# hd-gs.net
KiCad netlist of a schematic drawn in Altium Designer
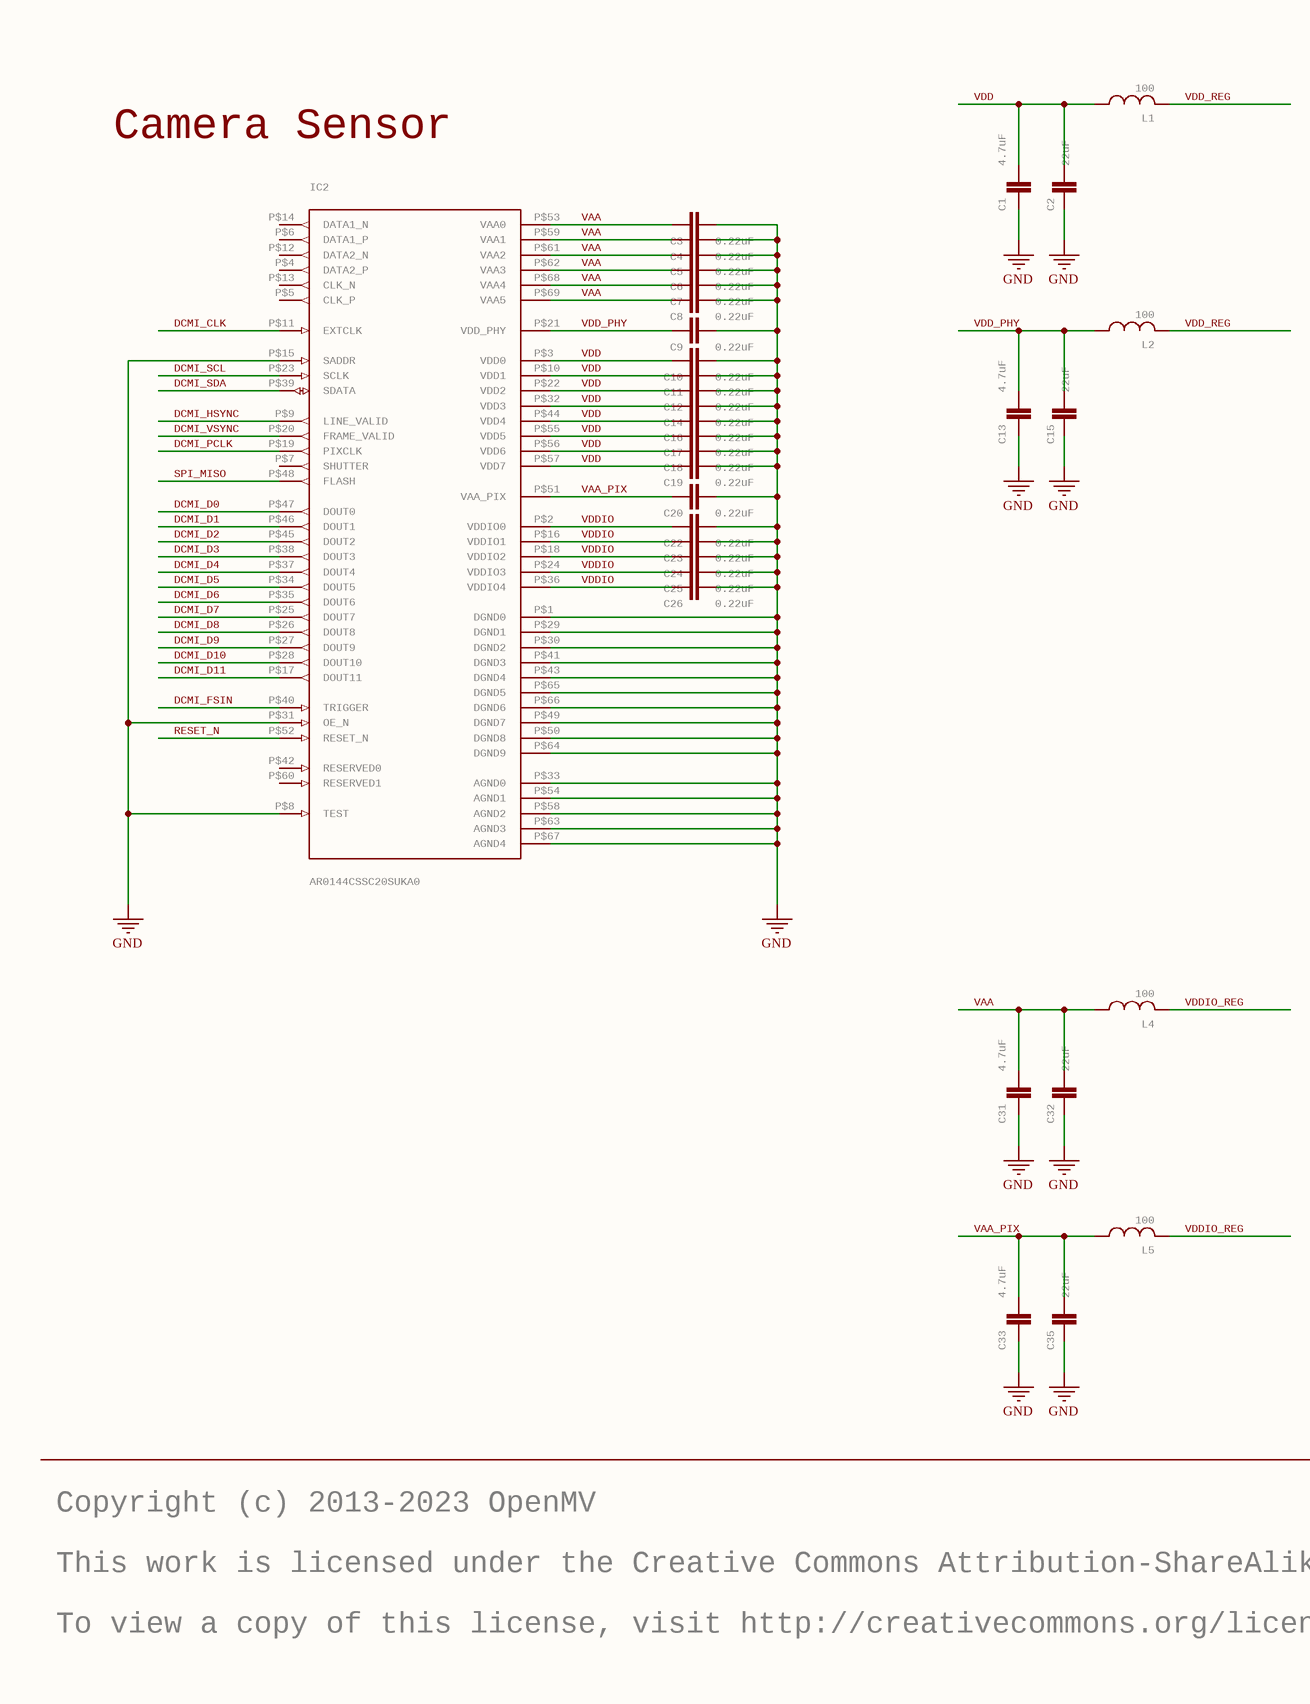
[diagram p0: hd-gs.SchDoc, left]
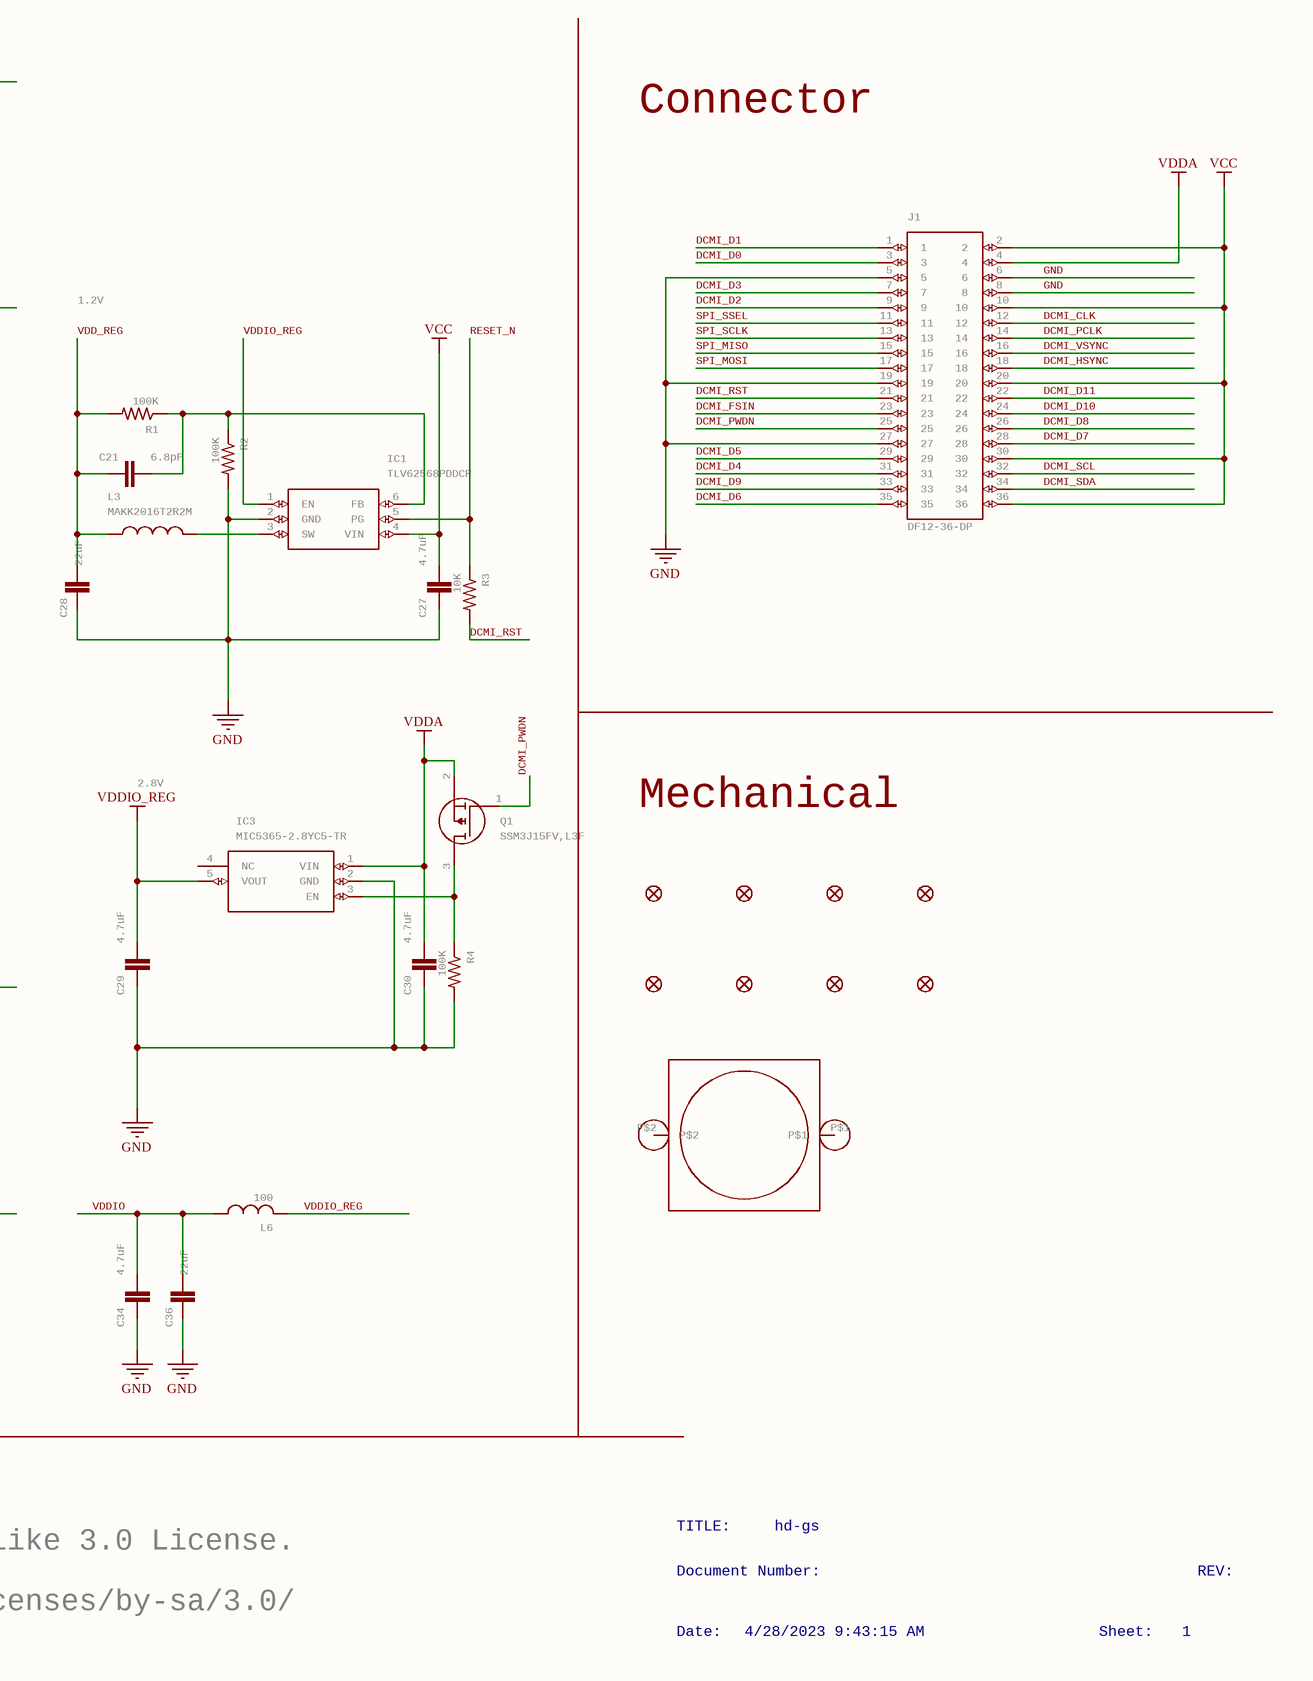
[diagram p1: hd-gs.SchDoc, right]

(export (version "E")
  (design (tool "Eeschema 10.0.6"))
  (components
    (comp (ref "C1")
      (value "4.7uF")
      (footprint "0402")
      (description "0402 (1005 Metric) Nick Garner - TeleSense")
      (fields (field (name "MPN") "JMK105BBJ475MV-F"))
      (libsource (lib "") (part "CAP_0402_1"))
    )
    (comp (ref "C2")
      (value "22uF")
      (footprint "0805")
      (fields (field (name "MPN") "CL21A226MQQNNNE"))
      (libsource (lib "camera-modules") (part "22UF-0805-6.3V-20%"))
    )
    (comp (ref "C3")
      (value "0.22uF")
      (footprint "C0201")
      (description "CAPACITOR, European symbol")
      (fields (field (name "MPN") "GRM033R60J224ME15D"))
      (libsource (lib "camera-modules") (part "C-EUC0201"))
    )
    (comp (ref "C4")
      (value "0.22uF")
      (footprint "C0201")
      (description "CAPACITOR, European symbol")
      (fields (field (name "MPN") "GRM033R60J224ME15D"))
      (libsource (lib "camera-modules") (part "C-EUC0201"))
    )
    (comp (ref "C5")
      (value "0.22uF")
      (footprint "C0201")
      (description "CAPACITOR, European symbol")
      (fields (field (name "MPN") "GRM033R60J224ME15D"))
      (libsource (lib "camera-modules") (part "C-EUC0201"))
    )
    (comp (ref "C6")
      (value "0.22uF")
      (footprint "C0201")
      (description "CAPACITOR, European symbol")
      (fields (field (name "MPN") "GRM033R60J224ME15D"))
      (libsource (lib "camera-modules") (part "C-EUC0201"))
    )
    (comp (ref "C7")
      (value "0.22uF")
      (footprint "C0201")
      (description "CAPACITOR, European symbol")
      (fields (field (name "MPN") "GRM033R60J224ME15D"))
      (libsource (lib "camera-modules") (part "C-EUC0201"))
    )
    (comp (ref "C8")
      (value "0.22uF")
      (footprint "C0201")
      (description "CAPACITOR, European symbol")
      (fields (field (name "MPN") "GRM033R60J224ME15D"))
      (libsource (lib "camera-modules") (part "C-EUC0201"))
    )
    (comp (ref "C9")
      (value "0.22uF")
      (footprint "C0201")
      (description "CAPACITOR, European symbol")
      (fields (field (name "MPN") "GRM033R60J224ME15D"))
      (libsource (lib "camera-modules") (part "C-EUC0201"))
    )
    (comp (ref "C10")
      (value "0.22uF")
      (footprint "C0201")
      (description "CAPACITOR, European symbol")
      (fields (field (name "MPN") "GRM033R60J224ME15D"))
      (libsource (lib "camera-modules") (part "C-EUC0201"))
    )
    (comp (ref "C11")
      (value "0.22uF")
      (footprint "C0201")
      (description "CAPACITOR, European symbol")
      (fields (field (name "MPN") "GRM033R60J224ME15D"))
      (libsource (lib "camera-modules") (part "C-EUC0201"))
    )
    (comp (ref "C12")
      (value "0.22uF")
      (footprint "C0201")
      (description "CAPACITOR, European symbol")
      (fields (field (name "MPN") "GRM033R60J224ME15D"))
      (libsource (lib "camera-modules") (part "C-EUC0201"))
    )
    (comp (ref "C13")
      (value "4.7uF")
      (footprint "0402")
      (description "0402 (1005 Metric) Nick Garner - TeleSense")
      (fields (field (name "MPN") "JMK105BBJ475MV-F"))
      (libsource (lib "") (part "CAP_0402_1"))
    )
    (comp (ref "C14")
      (value "0.22uF")
      (footprint "C0201")
      (description "CAPACITOR, European symbol")
      (fields (field (name "MPN") "GRM033R60J224ME15D"))
      (libsource (lib "camera-modules") (part "C-EUC0201"))
    )
    (comp (ref "C15")
      (value "22uF")
      (footprint "0805")
      (fields (field (name "MPN") "CL21A226MQQNNNE"))
      (libsource (lib "camera-modules") (part "22UF-0805-6.3V-20%"))
    )
    (comp (ref "C16")
      (value "0.22uF")
      (footprint "C0201")
      (description "CAPACITOR, European symbol")
      (fields (field (name "MPN") "GRM033R60J224ME15D"))
      (libsource (lib "camera-modules") (part "C-EUC0201"))
    )
    (comp (ref "C17")
      (value "0.22uF")
      (footprint "C0201")
      (description "CAPACITOR, European symbol")
      (fields (field (name "MPN") "GRM033R60J224ME15D"))
      (libsource (lib "camera-modules") (part "C-EUC0201"))
    )
    (comp (ref "C18")
      (value "0.22uF")
      (footprint "C0201")
      (description "CAPACITOR, European symbol")
      (fields (field (name "MPN") "GRM033R60J224ME15D"))
      (libsource (lib "camera-modules") (part "C-EUC0201"))
    )
    (comp (ref "C19")
      (value "0.22uF")
      (footprint "C0201")
      (description "CAPACITOR, European symbol")
      (fields (field (name "MPN") "GRM033R60J224ME15D"))
      (libsource (lib "camera-modules") (part "C-EUC0201"))
    )
    (comp (ref "C20")
      (value "0.22uF")
      (footprint "C0201")
      (description "CAPACITOR, European symbol")
      (fields (field (name "MPN") "GRM033R60J224ME15D"))
      (libsource (lib "camera-modules") (part "C-EUC0201"))
    )
    (comp (ref "C21")
      (value "6.8pF")
      (footprint "0402")
      (description "0402 (1005 Metric) Nick Garner - TeleSense")
      (fields (field (name "MPN") "GRM1555C1H6R8DA01D"))
      (libsource (lib "camera-modules") (part "CAP_0402"))
    )
    (comp (ref "C22")
      (value "0.22uF")
      (footprint "C0201")
      (description "CAPACITOR, European symbol")
      (fields (field (name "MPN") "GRM033R60J224ME15D"))
      (libsource (lib "camera-modules") (part "C-EUC0201"))
    )
    (comp (ref "C23")
      (value "0.22uF")
      (footprint "C0201")
      (description "CAPACITOR, European symbol")
      (fields (field (name "MPN") "GRM033R60J224ME15D"))
      (libsource (lib "camera-modules") (part "C-EUC0201"))
    )
    (comp (ref "C24")
      (value "0.22uF")
      (footprint "C0201")
      (description "CAPACITOR, European symbol")
      (fields (field (name "MPN") "GRM033R60J224ME15D"))
      (libsource (lib "camera-modules") (part "C-EUC0201"))
    )
    (comp (ref "C25")
      (value "0.22uF")
      (footprint "C0201")
      (description "CAPACITOR, European symbol")
      (fields (field (name "MPN") "GRM033R60J224ME15D"))
      (libsource (lib "camera-modules") (part "C-EUC0201"))
    )
    (comp (ref "C26")
      (value "0.22uF")
      (footprint "C0201")
      (description "CAPACITOR, European symbol")
      (fields (field (name "MPN") "GRM033R60J224ME15D"))
      (libsource (lib "camera-modules") (part "C-EUC0201"))
    )
    (comp (ref "C27")
      (value "4.7uF")
      (footprint "0402")
      (description "0402 (1005 Metric) Nick Garner - TeleSense")
      (fields (field (name "MPN") "JMK105BBJ475MV-F"))
      (libsource (lib "") (part "CAP_0402_1"))
    )
    (comp (ref "C28")
      (value "22uF")
      (footprint "0805")
      (fields (field (name "MPN") "CL21A226MQQNNNE"))
      (libsource (lib "camera-modules") (part "22UF-0805-6.3V-20%"))
    )
    (comp (ref "C29")
      (value "4.7uF")
      (footprint "0402")
      (description "0402 (1005 Metric) Nick Garner - TeleSense")
      (fields (field (name "MPN") "JMK105BBJ475MV-F"))
      (libsource (lib "") (part "CAP_0402_1"))
    )
    (comp (ref "C30")
      (value "4.7uF")
      (footprint "0402")
      (description "0402 (1005 Metric) Nick Garner - TeleSense")
      (fields (field (name "MPN") "JMK105BBJ475MV-F"))
      (libsource (lib "") (part "CAP_0402_1"))
    )
    (comp (ref "C31")
      (value "4.7uF")
      (footprint "0402")
      (description "0402 (1005 Metric) Nick Garner - TeleSense")
      (fields (field (name "MPN") "JMK105BBJ475MV-F"))
      (libsource (lib "") (part "CAP_0402_1"))
    )
    (comp (ref "C32")
      (value "22uF")
      (footprint "0805")
      (fields (field (name "MPN") "CL21A226MQQNNNE"))
      (libsource (lib "camera-modules") (part "22UF-0805-6.3V-20%"))
    )
    (comp (ref "C33")
      (value "4.7uF")
      (footprint "0402")
      (description "0402 (1005 Metric) Nick Garner - TeleSense")
      (fields (field (name "MPN") "JMK105BBJ475MV-F"))
      (libsource (lib "") (part "CAP_0402_1"))
    )
    (comp (ref "C34")
      (value "4.7uF")
      (footprint "0402")
      (description "0402 (1005 Metric) Nick Garner - TeleSense")
      (fields (field (name "MPN") "JMK105BBJ475MV-F"))
      (libsource (lib "") (part "CAP_0402_1"))
    )
    (comp (ref "C35")
      (value "22uF")
      (footprint "0805")
      (fields (field (name "MPN") "CL21A226MQQNNNE"))
      (libsource (lib "camera-modules") (part "22UF-0805-6.3V-20%"))
    )
    (comp (ref "C36")
      (value "22uF")
      (footprint "0805")
      (fields (field (name "MPN") "CL21A226MQQNNNE"))
      (libsource (lib "camera-modules") (part "22UF-0805-6.3V-20%"))
    )
    (comp (ref "FD1")
      (value "FIDUCIAL1X2")
      (footprint "FIDUCIAL-1X2")
      (fields (field (name "LIBRARYNAME") "SparkFun-Aesthetics"))
      (libsource (lib "camera-modules") (part "FIDUCIAL1X2"))
    )
    (comp (ref "FD2")
      (value "FIDUCIAL1X2")
      (footprint "FIDUCIAL-1X2")
      (fields (field (name "LIBRARYNAME") "SparkFun-Aesthetics"))
      (libsource (lib "camera-modules") (part "FIDUCIAL1X2"))
    )
    (comp (ref "FD3")
      (value "FIDUCIAL1X2")
      (footprint "FIDUCIAL-1X2")
      (fields (field (name "LIBRARYNAME") "SparkFun-Aesthetics"))
      (libsource (lib "camera-modules") (part "FIDUCIAL1X2"))
    )
    (comp (ref "FD4")
      (value "FIDUCIAL1X2")
      (footprint "FIDUCIAL-1X2")
      (fields (field (name "LIBRARYNAME") "SparkFun-Aesthetics"))
      (libsource (lib "camera-modules") (part "FIDUCIAL1X2"))
    )
    (comp (ref "FD5")
      (value "FIDUCIAL1X2")
      (footprint "FIDUCIAL-1X2")
      (fields (field (name "LIBRARYNAME") "SparkFun-Aesthetics"))
      (libsource (lib "camera-modules") (part "FIDUCIAL1X2"))
    )
    (comp (ref "FD6")
      (value "FIDUCIAL1X2")
      (footprint "FIDUCIAL-1X2")
      (fields (field (name "LIBRARYNAME") "SparkFun-Aesthetics"))
      (libsource (lib "camera-modules") (part "FIDUCIAL1X2"))
    )
    (comp (ref "FD7")
      (value "FIDUCIAL1X2")
      (footprint "FIDUCIAL-1X2")
      (fields (field (name "LIBRARYNAME") "SparkFun-Aesthetics"))
      (libsource (lib "camera-modules") (part "FIDUCIAL1X2"))
    )
    (comp (ref "FD8")
      (value "FIDUCIAL1X2")
      (footprint "FIDUCIAL-1X2")
      (fields (field (name "LIBRARYNAME") "SparkFun-Aesthetics"))
      (libsource (lib "camera-modules") (part "FIDUCIAL1X2"))
    )
    (comp (ref "H1")
      (value "LENSMOUNT20MM")
      (footprint "LENSMOUNT-20MM")
      (libsource (lib "camera-modules") (part "LENSMOUNT20MM"))
    )
    (comp (ref "IC1")
      (value "TLV62568PDDCR")
      (footprint "SOT95P280X110-6N")
      (fields (field (name "MOUSER_PART_NUMBER") "595-TLV62568PDDCR"))
      (libsource (lib "camera-modules") (part "TLV62568PDDCR"))
    )
    (comp (ref "IC2")
      (value "AR0144CSSC20SUKA0")
      (footprint "AR0144CSSC20SUKA0")
      (fields (field (name "MPN") "AR0144CSSC20SUKA0-CRBR"))
      (libsource (lib "camera-modules") (part "AR0144CSSC20SUKA0"))
    )
    (comp (ref "IC3")
      (value "MIC5365-2.8YC5-TR")
      (footprint "SOT65P210X110-5N")
      (description "IC REG LINEAR 2.8V 150MA SC70-5   Source:  Datasheet")
      (fields (field (name "MOUSER_PART_NUMBER") "998-MIC5365-2.8YC5TR"))
      (libsource (lib "camera-modules") (part "MIC5365-2.8YC5-TR"))
    )
    (comp (ref "J1")
      (value "DF12-36-DP")
      (footprint "DF12-36-DP")
      (fields (field (name "MPN") "DF12NB(3.0)-36DP-0.5V(51)"))
      (libsource (lib "camera-modules") (part "DF12-36-DP"))
    )
    (comp (ref "L1")
      (value "100")
      (footprint "0402")
      (fields (field (name "MPN") "MFBM1V1005-101-R"))
      (libsource (lib "camera-modules") (part "INDUCTOR_0402"))
    )
    (comp (ref "L2")
      (value "100")
      (footprint "0402")
      (fields (field (name "MPN") "MFBM1V1005-101-R"))
      (libsource (lib "camera-modules") (part "INDUCTOR_0402"))
    )
    (comp (ref "L3")
      (value "MAKK2016T2R2M")
      (footprint "INDC2016X100N")
      (description "INDUCTOR, METAL CORE Check availability")
      (fields (field (name "MF") "Taiyo Yuden"))
      (libsource (lib "camera-modules") (part "MAKK2016T2R2M"))
    )
    (comp (ref "L4")
      (value "100")
      (footprint "0402")
      (fields (field (name "MPN") "MFBM1V1005-101-R"))
      (libsource (lib "camera-modules") (part "INDUCTOR_0402"))
    )
    (comp (ref "L5")
      (value "100")
      (footprint "0402")
      (fields (field (name "MPN") "MFBM1V1005-101-R"))
      (libsource (lib "camera-modules") (part "INDUCTOR_0402"))
    )
    (comp (ref "L6")
      (value "100")
      (footprint "0402")
      (fields (field (name "MPN") "MFBM1V1005-101-R"))
      (libsource (lib "camera-modules") (part "INDUCTOR_0402"))
    )
    (comp (ref "Q1")
      (value "SSM3J15FV,L3F")
      (footprint "SSM3J15FV")
      (description "MOSFET 30 V, P-channel Trench MOSFET   Source:  Datasheet")
      (libsource (lib "camera-modules") (part "PMXB120EPEZ"))
    )
    (comp (ref "R1")
      (value "100K")
      (footprint "R0402")
      (description "RESISTOR, American symbol")
      (fields (field (name "MPN") "AC0402FR-07100KL"))
      (libsource (lib "camera-modules") (part "R-US_R0402"))
    )
    (comp (ref "R2")
      (value "100K")
      (footprint "R0402")
      (description "RESISTOR, American symbol")
      (fields (field (name "MPN") "AC0402FR-07100KL"))
      (libsource (lib "camera-modules") (part "R-US_R0402"))
    )
    (comp (ref "R3")
      (value "10K")
      (footprint "R0402")
      (description "RESISTOR, American symbol")
      (fields (field (name "MPN") "AC0402FR-1310KL"))
      (libsource (lib "camera-modules") (part "R-US_R0402"))
    )
    (comp (ref "R4")
      (value "100K")
      (footprint "R0402")
      (description "RESISTOR, American symbol")
      (fields (field (name "MPN") "AC0402FR-07100KL"))
      (libsource (lib "camera-modules") (part "R-US_R0402"))
    )
  )
  (nets
    (net (code "1") (name "/DCMI_CLK") (class "Default")
      (node (ref "IC2") (pin "P$11") (pinfunction "EXTCLK_P$11") (pintype "input"))
      (node (ref "J1") (pin "12") (pinfunction "12_12") (pintype "bidirectional"))
    )
    (net (code "2") (name "/DCMI_D0") (class "Default")
      (node (ref "IC2") (pin "P$47") (pinfunction "DOUT0_P$47") (pintype "output"))
      (node (ref "J1") (pin "3") (pinfunction "3_3") (pintype "bidirectional"))
    )
    (net (code "3") (name "/DCMI_D1") (class "Default")
      (node (ref "IC2") (pin "P$46") (pinfunction "DOUT1_P$46") (pintype "output"))
      (node (ref "J1") (pin "1") (pinfunction "1_1") (pintype "bidirectional"))
    )
    (net (code "4") (name "/DCMI_D2") (class "Default")
      (node (ref "IC2") (pin "P$45") (pinfunction "DOUT2_P$45") (pintype "output"))
      (node (ref "J1") (pin "9") (pinfunction "9_9") (pintype "bidirectional"))
    )
    (net (code "5") (name "/DCMI_D3") (class "Default")
      (node (ref "IC2") (pin "P$38") (pinfunction "DOUT3_P$38") (pintype "output"))
      (node (ref "J1") (pin "7") (pinfunction "7_7") (pintype "bidirectional"))
    )
    (net (code "6") (name "/DCMI_D4") (class "Default")
      (node (ref "IC2") (pin "P$37") (pinfunction "DOUT4_P$37") (pintype "output"))
      (node (ref "J1") (pin "31") (pinfunction "31_31") (pintype "bidirectional"))
    )
    (net (code "7") (name "/DCMI_D5") (class "Default")
      (node (ref "IC2") (pin "P$34") (pinfunction "DOUT5_P$34") (pintype "output"))
      (node (ref "J1") (pin "29") (pinfunction "29_29") (pintype "bidirectional"))
    )
    (net (code "8") (name "/DCMI_D6") (class "Default")
      (node (ref "IC2") (pin "P$35") (pinfunction "DOUT6_P$35") (pintype "output"))
      (node (ref "J1") (pin "35") (pinfunction "35_35") (pintype "bidirectional"))
    )
    (net (code "9") (name "/DCMI_D7") (class "Default")
      (node (ref "IC2") (pin "P$25") (pinfunction "DOUT7_P$25") (pintype "output"))
      (node (ref "J1") (pin "28") (pinfunction "28_28") (pintype "bidirectional"))
    )
    (net (code "10") (name "/DCMI_D8") (class "Default")
      (node (ref "IC2") (pin "P$26") (pinfunction "DOUT8_P$26") (pintype "output"))
      (node (ref "J1") (pin "26") (pinfunction "26_26") (pintype "bidirectional"))
    )
    (net (code "11") (name "/DCMI_D9") (class "Default")
      (node (ref "IC2") (pin "P$27") (pinfunction "DOUT9_P$27") (pintype "output"))
      (node (ref "J1") (pin "33") (pinfunction "33_33") (pintype "bidirectional"))
    )
    (net (code "12") (name "/DCMI_D10") (class "Default")
      (node (ref "IC2") (pin "P$28") (pinfunction "DOUT10_P$28") (pintype "output"))
      (node (ref "J1") (pin "24") (pinfunction "24_24") (pintype "bidirectional"))
    )
    (net (code "13") (name "/DCMI_D11") (class "Default")
      (node (ref "IC2") (pin "P$17") (pinfunction "DOUT11_P$17") (pintype "output"))
      (node (ref "J1") (pin "22") (pinfunction "22_22") (pintype "bidirectional"))
    )
    (net (code "14") (name "/DCMI_FSIN") (class "Default")
      (node (ref "IC2") (pin "P$40") (pinfunction "TRIGGER_P$40") (pintype "input"))
      (node (ref "J1") (pin "23") (pinfunction "23_23") (pintype "bidirectional"))
    )
    (net (code "15") (name "/DCMI_HSYNC") (class "Default")
      (node (ref "IC2") (pin "P$9") (pinfunction "LINE_VALID_P$9") (pintype "output"))
      (node (ref "J1") (pin "18") (pinfunction "18_18") (pintype "bidirectional"))
    )
    (net (code "16") (name "/DCMI_PCLK") (class "Default")
      (node (ref "IC2") (pin "P$19") (pinfunction "PIXCLK_P$19") (pintype "output"))
      (node (ref "J1") (pin "14") (pinfunction "14_14") (pintype "bidirectional"))
    )
    (net (code "17") (name "/DCMI_PWDN") (class "Default")
      (node (ref "J1") (pin "25") (pinfunction "25_25") (pintype "bidirectional"))
      (node (ref "Q1") (pin "1") (pinfunction "G_1") (pintype "bidirectional"))
    )
    (net (code "18") (name "/DCMI_RST") (class "Default")
      (node (ref "J1") (pin "21") (pinfunction "21_21") (pintype "bidirectional"))
      (node (ref "R3") (pin "2") (pinfunction "2_2") (pintype "passive"))
    )
    (net (code "19") (name "/DCMI_SCL") (class "Default")
      (node (ref "IC2") (pin "P$23") (pinfunction "SCLK_P$23") (pintype "input"))
      (node (ref "J1") (pin "32") (pinfunction "32_32") (pintype "bidirectional"))
    )
    (net (code "20") (name "/DCMI_SDA") (class "Default")
      (node (ref "IC2") (pin "P$39") (pinfunction "SDATA_P$39") (pintype "bidirectional"))
      (node (ref "J1") (pin "34") (pinfunction "34_34") (pintype "bidirectional"))
    )
    (net (code "21") (name "/DCMI_VSYNC") (class "Default")
      (node (ref "IC2") (pin "P$20") (pinfunction "FRAME_VALID_P$20") (pintype "output"))
      (node (ref "J1") (pin "16") (pinfunction "16_16") (pintype "bidirectional"))
    )
    (net (code "22") (name "/RESET_N") (class "Default")
      (node (ref "IC1") (pin "5") (pinfunction "PG_5") (pintype "bidirectional"))
      (node (ref "IC2") (pin "P$52") (pinfunction "RESET_N_P$52") (pintype "input"))
      (node (ref "R3") (pin "1") (pinfunction "1_1") (pintype "passive"))
    )
    (net (code "23") (name "/SPI_MISO") (class "Default")
      (node (ref "IC2") (pin "P$48") (pinfunction "FLASH_P$48") (pintype "output"))
      (node (ref "J1") (pin "15") (pinfunction "15_15") (pintype "bidirectional"))
    )
    (net (code "24") (name "/SPI_MOSI") (class "Default")
      (node (ref "J1") (pin "17") (pinfunction "17_17") (pintype "bidirectional"))
    )
    (net (code "25") (name "/SPI_SCLK") (class "Default")
      (node (ref "J1") (pin "13") (pinfunction "13_13") (pintype "bidirectional"))
    )
    (net (code "26") (name "/SPI_SSEL") (class "Default")
      (node (ref "J1") (pin "11") (pinfunction "11_11") (pintype "bidirectional"))
    )
    (net (code "27") (name "/VAA") (class "Default")
      (node (ref "C3") (pin "1") (pinfunction "1_1") (pintype "passive"))
      (node (ref "C31") (pin "2") (pinfunction "2_2") (pintype "passive"))
      (node (ref "C32") (pin "2") (pinfunction "2_2") (pintype "passive"))
      (node (ref "C4") (pin "1") (pinfunction "1_1") (pintype "passive"))
      (node (ref "C5") (pin "1") (pinfunction "1_1") (pintype "passive"))
      (node (ref "C6") (pin "1") (pinfunction "1_1") (pintype "passive"))
      (node (ref "C7") (pin "1") (pinfunction "1_1") (pintype "passive"))
      (node (ref "C8") (pin "1") (pinfunction "1_1") (pintype "passive"))
      (node (ref "IC2") (pin "P$53") (pinfunction "VAA0_P$53") (pintype "power_in"))
      (node (ref "IC2") (pin "P$59") (pinfunction "VAA1_P$59") (pintype "power_in"))
      (node (ref "IC2") (pin "P$61") (pinfunction "VAA2_P$61") (pintype "power_in"))
      (node (ref "IC2") (pin "P$62") (pinfunction "VAA3_P$62") (pintype "power_in"))
      (node (ref "IC2") (pin "P$68") (pinfunction "VAA4_P$68") (pintype "power_in"))
      (node (ref "IC2") (pin "P$69") (pinfunction "VAA5_P$69") (pintype "power_in"))
      (node (ref "L4") (pin "1") (pinfunction "P$1_1") (pintype "passive"))
    )
    (net (code "28") (name "/VAA_PIX") (class "Default")
      (node (ref "C20") (pin "1") (pinfunction "1_1") (pintype "passive"))
      (node (ref "C33") (pin "2") (pinfunction "2_2") (pintype "passive"))
      (node (ref "C35") (pin "2") (pinfunction "2_2") (pintype "passive"))
      (node (ref "IC2") (pin "P$51") (pinfunction "VAA_PIX_P$51") (pintype "power_in"))
      (node (ref "L5") (pin "1") (pinfunction "P$1_1") (pintype "passive"))
    )
    (net (code "29") (name "/VDD") (class "Default")
      (node (ref "C1") (pin "2") (pinfunction "2_2") (pintype "passive"))
      (node (ref "C10") (pin "1") (pinfunction "1_1") (pintype "passive"))
      (node (ref "C11") (pin "1") (pinfunction "1_1") (pintype "passive"))
      (node (ref "C12") (pin "1") (pinfunction "1_1") (pintype "passive"))
      (node (ref "C14") (pin "1") (pinfunction "1_1") (pintype "passive"))
      (node (ref "C16") (pin "1") (pinfunction "1_1") (pintype "passive"))
      (node (ref "C17") (pin "1") (pinfunction "1_1") (pintype "passive"))
      (node (ref "C18") (pin "1") (pinfunction "1_1") (pintype "passive"))
      (node (ref "C19") (pin "1") (pinfunction "1_1") (pintype "passive"))
      (node (ref "C2") (pin "2") (pinfunction "2_2") (pintype "passive"))
      (node (ref "IC2") (pin "P$10") (pinfunction "VDD1_P$10") (pintype "power_in"))
      (node (ref "IC2") (pin "P$22") (pinfunction "VDD2_P$22") (pintype "power_in"))
      (node (ref "IC2") (pin "P$3") (pinfunction "VDD0_P$3") (pintype "power_in"))
      (node (ref "IC2") (pin "P$32") (pinfunction "VDD3_P$32") (pintype "power_in"))
      (node (ref "IC2") (pin "P$44") (pinfunction "VDD4_P$44") (pintype "power_in"))
      (node (ref "IC2") (pin "P$55") (pinfunction "VDD5_P$55") (pintype "power_in"))
      (node (ref "IC2") (pin "P$56") (pinfunction "VDD6_P$56") (pintype "power_in"))
      (node (ref "IC2") (pin "P$57") (pinfunction "VDD7_P$57") (pintype "power_in"))
      (node (ref "L1") (pin "1") (pinfunction "P$1_1") (pintype "passive"))
    )
    (net (code "30") (name "/VDDIO") (class "Default")
      (node (ref "C22") (pin "1") (pinfunction "1_1") (pintype "passive"))
      (node (ref "C23") (pin "1") (pinfunction "1_1") (pintype "passive"))
      (node (ref "C24") (pin "1") (pinfunction "1_1") (pintype "passive"))
      (node (ref "C25") (pin "1") (pinfunction "1_1") (pintype "passive"))
      (node (ref "C26") (pin "1") (pinfunction "1_1") (pintype "passive"))
      (node (ref "C34") (pin "2") (pinfunction "2_2") (pintype "passive"))
      (node (ref "C36") (pin "2") (pinfunction "2_2") (pintype "passive"))
      (node (ref "IC2") (pin "P$16") (pinfunction "VDDIO1_P$16") (pintype "power_in"))
      (node (ref "IC2") (pin "P$18") (pinfunction "VDDIO2_P$18") (pintype "power_in"))
      (node (ref "IC2") (pin "P$2") (pinfunction "VDDIO0_P$2") (pintype "power_in"))
      (node (ref "IC2") (pin "P$24") (pinfunction "VDDIO3_P$24") (pintype "power_in"))
      (node (ref "IC2") (pin "P$36") (pinfunction "VDDIO4_P$36") (pintype "power_in"))
      (node (ref "L6") (pin "1") (pinfunction "P$1_1") (pintype "passive"))
    )
    (net (code "31") (name "/VDD_PHY") (class "Default")
      (node (ref "C13") (pin "2") (pinfunction "2_2") (pintype "passive"))
      (node (ref "C15") (pin "2") (pinfunction "2_2") (pintype "passive"))
      (node (ref "C9") (pin "1") (pinfunction "1_1") (pintype "passive"))
      (node (ref "IC2") (pin "P$21") (pinfunction "VDD_PHY_P$21") (pintype "power_in"))
      (node (ref "L2") (pin "1") (pinfunction "P$1_1") (pintype "passive"))
    )
    (net (code "32") (name "/VDD_REG") (class "Default")
      (node (ref "C21") (pin "1") (pinfunction "1_1") (pintype "passive"))
      (node (ref "C28") (pin "2") (pinfunction "2_2") (pintype "passive"))
      (node (ref "L1") (pin "2") (pinfunction "P$2_2") (pintype "passive"))
      (node (ref "L2") (pin "2") (pinfunction "P$2_2") (pintype "passive"))
      (node (ref "L3") (pin "1") (pinfunction "1_1") (pintype "passive"))
      (node (ref "R1") (pin "2") (pinfunction "2_2") (pintype "passive"))
    )
    (net (code "33") (name "GND") (class "Default")
      (node (ref "C1") (pin "1") (pinfunction "1_1") (pintype "passive"))
      (node (ref "C10") (pin "2") (pinfunction "2_2") (pintype "passive"))
      (node (ref "C11") (pin "2") (pinfunction "2_2") (pintype "passive"))
      (node (ref "C12") (pin "2") (pinfunction "2_2") (pintype "passive"))
      (node (ref "C13") (pin "1") (pinfunction "1_1") (pintype "passive"))
      (node (ref "C14") (pin "2") (pinfunction "2_2") (pintype "passive"))
      (node (ref "C15") (pin "1") (pinfunction "1_1") (pintype "passive"))
      (node (ref "C16") (pin "2") (pinfunction "2_2") (pintype "passive"))
      (node (ref "C17") (pin "2") (pinfunction "2_2") (pintype "passive"))
      (node (ref "C18") (pin "2") (pinfunction "2_2") (pintype "passive"))
      (node (ref "C19") (pin "2") (pinfunction "2_2") (pintype "passive"))
      (node (ref "C2") (pin "1") (pinfunction "1_1") (pintype "passive"))
      (node (ref "C20") (pin "2") (pinfunction "2_2") (pintype "passive"))
      (node (ref "C22") (pin "2") (pinfunction "2_2") (pintype "passive"))
      (node (ref "C23") (pin "2") (pinfunction "2_2") (pintype "passive"))
      (node (ref "C24") (pin "2") (pinfunction "2_2") (pintype "passive"))
      (node (ref "C25") (pin "2") (pinfunction "2_2") (pintype "passive"))
      (node (ref "C26") (pin "2") (pinfunction "2_2") (pintype "passive"))
      (node (ref "C27") (pin "1") (pinfunction "1_1") (pintype "passive"))
      (node (ref "C28") (pin "1") (pinfunction "1_1") (pintype "passive"))
      (node (ref "C29") (pin "1") (pinfunction "1_1") (pintype "passive"))
      (node (ref "C3") (pin "2") (pinfunction "2_2") (pintype "passive"))
      (node (ref "C30") (pin "1") (pinfunction "1_1") (pintype "passive"))
      (node (ref "C31") (pin "1") (pinfunction "1_1") (pintype "passive"))
      (node (ref "C32") (pin "1") (pinfunction "1_1") (pintype "passive"))
      (node (ref "C33") (pin "1") (pinfunction "1_1") (pintype "passive"))
      (node (ref "C34") (pin "1") (pinfunction "1_1") (pintype "passive"))
      (node (ref "C35") (pin "1") (pinfunction "1_1") (pintype "passive"))
      (node (ref "C36") (pin "1") (pinfunction "1_1") (pintype "passive"))
      (node (ref "C4") (pin "2") (pinfunction "2_2") (pintype "passive"))
      (node (ref "C5") (pin "2") (pinfunction "2_2") (pintype "passive"))
      (node (ref "C6") (pin "2") (pinfunction "2_2") (pintype "passive"))
      (node (ref "C7") (pin "2") (pinfunction "2_2") (pintype "passive"))
      (node (ref "C8") (pin "2") (pinfunction "2_2") (pintype "passive"))
      (node (ref "C9") (pin "2") (pinfunction "2_2") (pintype "passive"))
      (node (ref "IC1") (pin "2") (pinfunction "GND_2") (pintype "bidirectional"))
      (node (ref "IC2") (pin "P$1") (pinfunction "DGND0_P$1") (pintype "power_in"))
      (node (ref "IC2") (pin "P$15") (pinfunction "SADDR_P$15") (pintype "input"))
      (node (ref "IC2") (pin "P$29") (pinfunction "DGND1_P$29") (pintype "power_in"))
      (node (ref "IC2") (pin "P$30") (pinfunction "DGND2_P$30") (pintype "power_in"))
      (node (ref "IC2") (pin "P$31") (pinfunction "OE_N_P$31") (pintype "input"))
      (node (ref "IC2") (pin "P$33") (pinfunction "AGND0_P$33") (pintype "power_in"))
      (node (ref "IC2") (pin "P$41") (pinfunction "DGND3_P$41") (pintype "power_in"))
      (node (ref "IC2") (pin "P$43") (pinfunction "DGND4_P$43") (pintype "power_in"))
      (node (ref "IC2") (pin "P$49") (pinfunction "DGND7_P$49") (pintype "power_in"))
      (node (ref "IC2") (pin "P$50") (pinfunction "DGND8_P$50") (pintype "power_in"))
      (node (ref "IC2") (pin "P$54") (pinfunction "AGND1_P$54") (pintype "power_in"))
      (node (ref "IC2") (pin "P$58") (pinfunction "AGND2_P$58") (pintype "power_in"))
      (node (ref "IC2") (pin "P$63") (pinfunction "AGND3_P$63") (pintype "power_in"))
      (node (ref "IC2") (pin "P$64") (pinfunction "DGND9_P$64") (pintype "power_in"))
      (node (ref "IC2") (pin "P$65") (pinfunction "DGND5_P$65") (pintype "power_in"))
      (node (ref "IC2") (pin "P$66") (pinfunction "DGND6_P$66") (pintype "power_in"))
      (node (ref "IC2") (pin "P$67") (pinfunction "AGND4_P$67") (pintype "power_in"))
      (node (ref "IC2") (pin "P$8") (pinfunction "TEST_P$8") (pintype "input"))
      (node (ref "IC3") (pin "2") (pinfunction "GND_2") (pintype "bidirectional"))
      (node (ref "J1") (pin "19") (pinfunction "19_19") (pintype "bidirectional"))
      (node (ref "J1") (pin "27") (pinfunction "27_27") (pintype "bidirectional"))
      (node (ref "J1") (pin "5") (pinfunction "5_5") (pintype "bidirectional"))
      (node (ref "J1") (pin "6") (pinfunction "6_6") (pintype "bidirectional"))
      (node (ref "J1") (pin "8") (pinfunction "8_8") (pintype "bidirectional"))
      (node (ref "R2") (pin "2") (pinfunction "2_2") (pintype "passive"))
      (node (ref "R4") (pin "2") (pinfunction "2_2") (pintype "passive"))
    )
    (net (code "34") (name "Net-(IC1-FB)") (class "Default")
      (node (ref "C21") (pin "2") (pinfunction "2_2") (pintype "passive"))
      (node (ref "IC1") (pin "6") (pinfunction "FB_6") (pintype "bidirectional"))
      (node (ref "R1") (pin "1") (pinfunction "1_1") (pintype "passive"))
      (node (ref "R2") (pin "1") (pinfunction "1_1") (pintype "passive"))
    )
    (net (code "35") (name "Net-(IC1-SW)") (class "Default")
      (node (ref "IC1") (pin "3") (pinfunction "SW_3") (pintype "bidirectional"))
      (node (ref "L3") (pin "2") (pinfunction "2_2") (pintype "passive"))
    )
    (net (code "36") (name "Net-(IC3-EN)") (class "Default")
      (node (ref "IC3") (pin "3") (pinfunction "EN_3") (pintype "bidirectional"))
      (node (ref "Q1") (pin "3") (pinfunction "D_3") (pintype "bidirectional"))
      (node (ref "R4") (pin "1") (pinfunction "1_1") (pintype "passive"))
    )
    (net (code "37") (name "VCC") (class "Default")
      (node (ref "C27") (pin "2") (pinfunction "2_2") (pintype "passive"))
      (node (ref "IC1") (pin "4") (pinfunction "VIN_4") (pintype "bidirectional"))
      (node (ref "J1") (pin "10") (pinfunction "10_10") (pintype "bidirectional"))
      (node (ref "J1") (pin "2") (pinfunction "2_2") (pintype "bidirectional"))
      (node (ref "J1") (pin "20") (pinfunction "20_20") (pintype "bidirectional"))
      (node (ref "J1") (pin "30") (pinfunction "30_30") (pintype "bidirectional"))
      (node (ref "J1") (pin "36") (pinfunction "36_36") (pintype "bidirectional"))
    )
    (net (code "38") (name "VDDA") (class "Default")
      (node (ref "C30") (pin "2") (pinfunction "2_2") (pintype "passive"))
      (node (ref "IC3") (pin "1") (pinfunction "VIN_1") (pintype "bidirectional"))
      (node (ref "J1") (pin "4") (pinfunction "4_4") (pintype "bidirectional"))
      (node (ref "Q1") (pin "2") (pinfunction "S_2") (pintype "bidirectional"))
    )
    (net (code "39") (name "VDDIO_REG") (class "Default")
      (node (ref "C29") (pin "2") (pinfunction "2_2") (pintype "passive"))
      (node (ref "IC1") (pin "1") (pinfunction "EN_1") (pintype "bidirectional"))
      (node (ref "IC3") (pin "5") (pinfunction "VOUT_5") (pintype "bidirectional"))
      (node (ref "L4") (pin "2") (pinfunction "P$2_2") (pintype "passive"))
      (node (ref "L5") (pin "2") (pinfunction "P$2_2") (pintype "passive"))
      (node (ref "L6") (pin "2") (pinfunction "P$2_2") (pintype "passive"))
    )
    (net (code "40") (name "unconnected-(H1-PadP$1)") (class "Default")
      (node (ref "H1") (pin "P$1") (pinfunction "P$1_P$1") (pintype "power_in"))
    )
    (net (code "41") (name "unconnected-(H1-PadP$2)") (class "Default")
      (node (ref "H1") (pin "P$2") (pinfunction "P$2_P$2") (pintype "power_in"))
    )
    (net (code "42") (name "unconnected-(IC2-CLK_N-PadP$13)") (class "Default")
      (node (ref "IC2") (pin "P$13") (pinfunction "CLK_N_P$13") (pintype "output"))
    )
    (net (code "43") (name "unconnected-(IC2-CLK_P-PadP$5)") (class "Default")
      (node (ref "IC2") (pin "P$5") (pinfunction "CLK_P_P$5") (pintype "output"))
    )
    (net (code "44") (name "unconnected-(IC2-DATA1_N-PadP$14)") (class "Default")
      (node (ref "IC2") (pin "P$14") (pinfunction "DATA1_N_P$14") (pintype "output"))
    )
    (net (code "45") (name "unconnected-(IC2-DATA1_P-PadP$6)") (class "Default")
      (node (ref "IC2") (pin "P$6") (pinfunction "DATA1_P_P$6") (pintype "output"))
    )
    (net (code "46") (name "unconnected-(IC2-DATA2_N-PadP$12)") (class "Default")
      (node (ref "IC2") (pin "P$12") (pinfunction "DATA2_N_P$12") (pintype "output"))
    )
    (net (code "47") (name "unconnected-(IC2-DATA2_P-PadP$4)") (class "Default")
      (node (ref "IC2") (pin "P$4") (pinfunction "DATA2_P_P$4") (pintype "output"))
    )
    (net (code "48") (name "unconnected-(IC2-RESERVED0-PadP$42)") (class "Default")
      (node (ref "IC2") (pin "P$42") (pinfunction "RESERVED0_P$42") (pintype "input"))
    )
    (net (code "49") (name "unconnected-(IC2-RESERVED1-PadP$60)") (class "Default")
      (node (ref "IC2") (pin "P$60") (pinfunction "RESERVED1_P$60") (pintype "input"))
    )
    (net (code "50") (name "unconnected-(IC2-SHUTTER-PadP$7)") (class "Default")
      (node (ref "IC2") (pin "P$7") (pinfunction "SHUTTER_P$7") (pintype "output"))
    )
    (net (code "51") (name "unconnected-(IC3-NC-Pad4)") (class "Default")
      (node (ref "IC3") (pin "4") (pinfunction "NC_4") (pintype "passive"))
    )
  )
)
